# openSipPuff.net
KiCad netlist of a schematic drawn in EAGLE
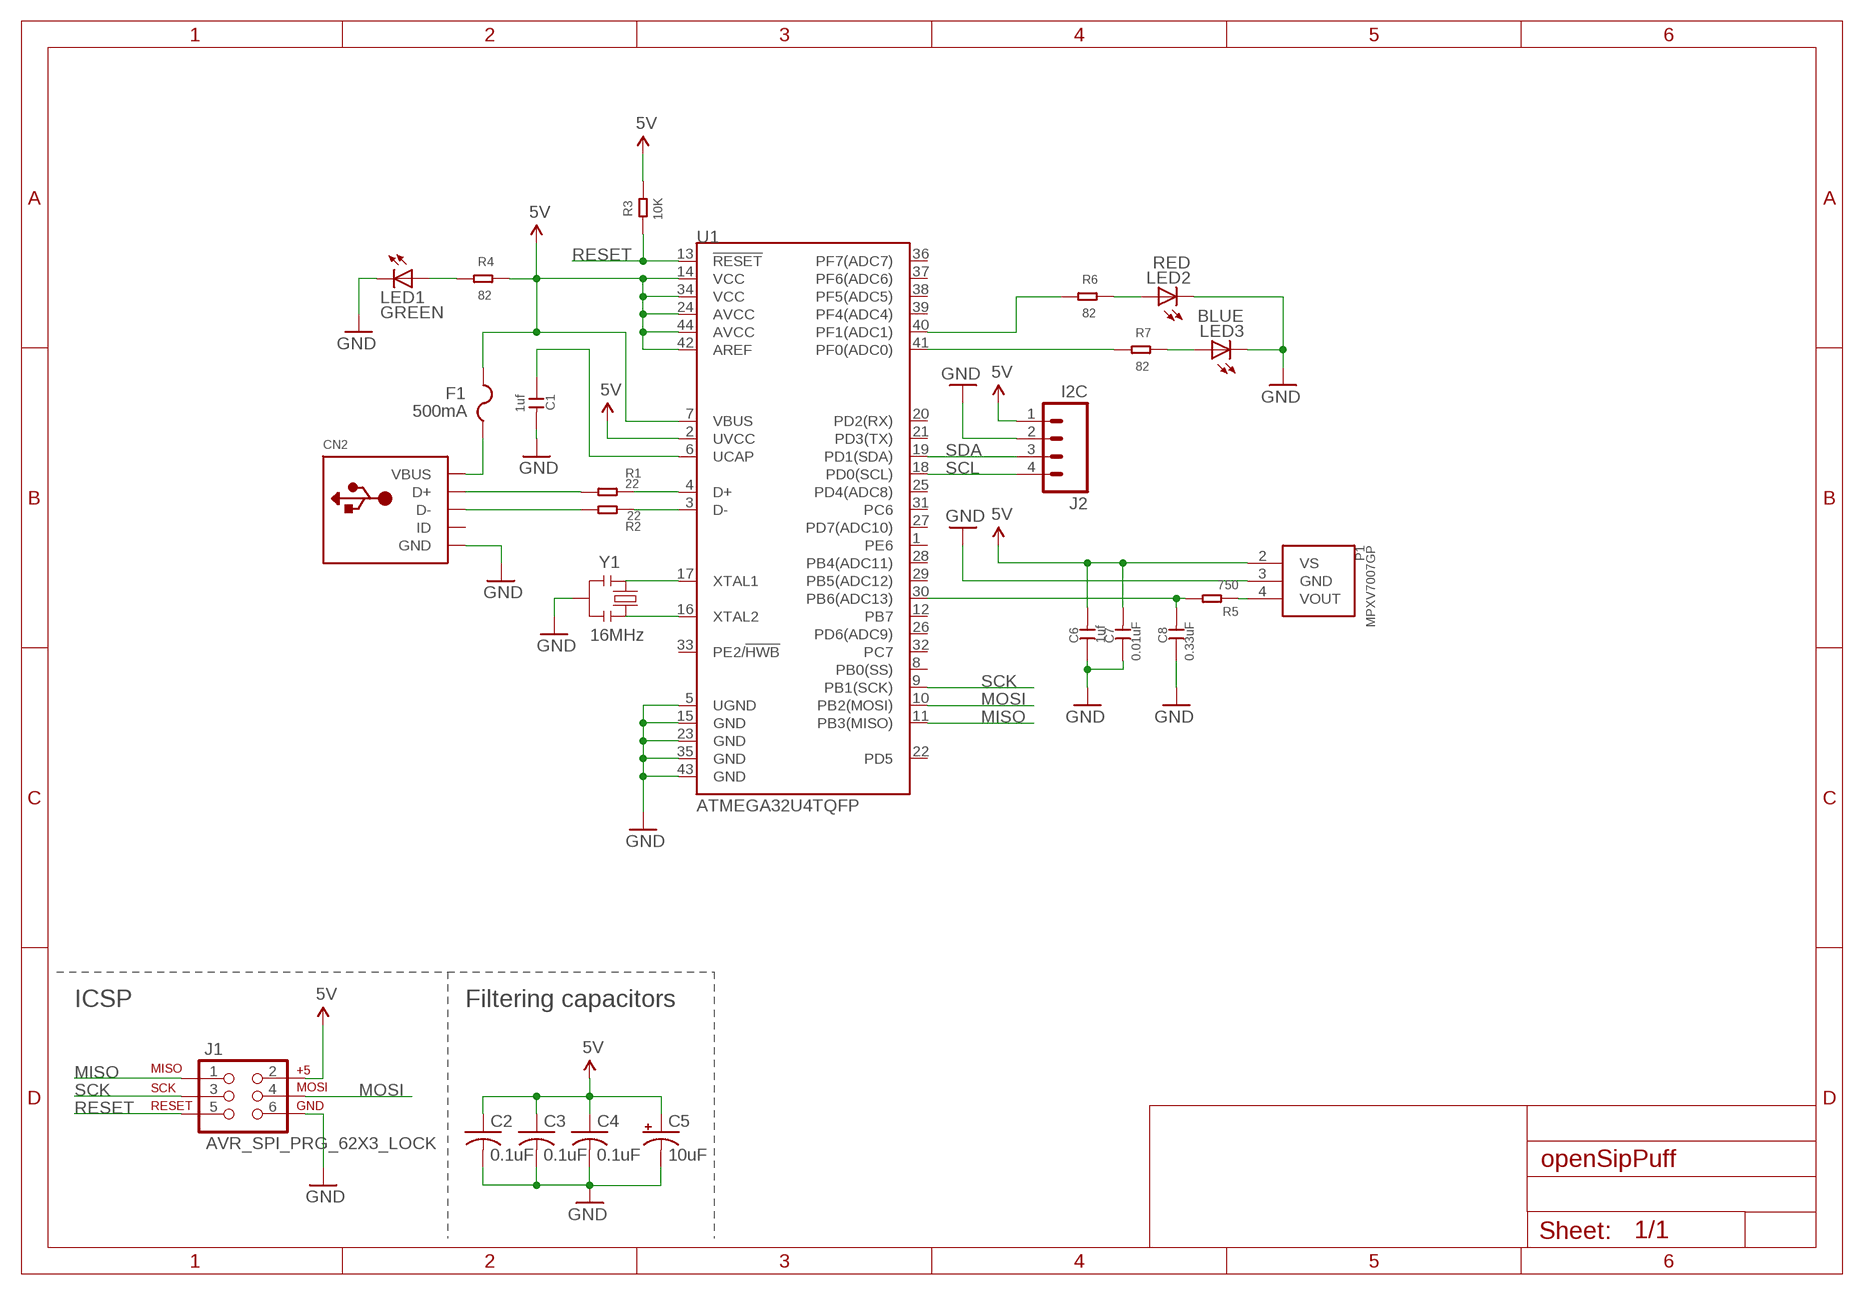
[diagram p0: schematic, sheet 1]

(export (version "E")
  (design (tool "Eeschema 10.0.6"))
  (components
    (comp (ref "C1")
      (value "1uf")
      (footprint "eagle-import:C0805")
      (fields (field (name "MPN") "CC0805KKX7R8BB105"))
      (libsource (lib "eagle-import") (part "CERAMIC-1UF-25V-10%-X7R(0805)"))
    )
    (comp (ref "C2")
      (value "0.1uF")
      (footprint "eagle-import:C0805K")
      (libsource (lib "eagle-import") (part "C-USC0805K"))
    )
    (comp (ref "C3")
      (value "0.1uF")
      (footprint "eagle-import:C0805K")
      (libsource (lib "eagle-import") (part "C-USC0805K"))
    )
    (comp (ref "C4")
      (value "0.1uF")
      (footprint "eagle-import:C0805K")
      (libsource (lib "eagle-import") (part "C-USC0805K"))
    )
    (comp (ref "C5")
      (value "10uF")
      (footprint "eagle-import:A_3216-18R")
      (libsource (lib "eagle-import") (part "CPOL-USA/3216-18R"))
    )
    (comp (ref "C6")
      (value "1uf")
      (footprint "eagle-import:C0805")
      (fields (field (name "MPN") "CC0805KKX7R8BB105"))
      (libsource (lib "eagle-import") (part "CERAMIC-1UF-25V-10%-X7R(0805)"))
    )
    (comp (ref "C7")
      (value "0.01uF")
      (footprint "eagle-import:C0805")
      (fields (field (name "MPN") "CC0805JRX7R9BB103"))
      (libsource (lib "eagle-import") (part "CERAMIC-10NF-50V-5%-X7R(0805)"))
    )
    (comp (ref "C8")
      (value "0.33uF")
      (footprint "eagle-import:C0805")
      (fields (field (name "MPN") "CC0805JRX7R9BB103"))
      (libsource (lib "eagle-import") (part "CERAMIC-10NF-50V-5%-X7R(0805)"))
    )
    (comp (ref "CN2")
      (value "USBMINIB")
      (footprint "eagle-import:USB-MINIB")
      (libsource (lib "eagle-import") (part "USBMINIB"))
    )
    (comp (ref "F1")
      (value "500mA")
      (footprint "eagle-import:R1206")
      (libsource (lib "eagle-import") (part "PTCFUSE-1206"))
    )
    (comp (ref "J1")
      (value "AVR_SPI_PRG_62X3_LOCK")
      (footprint "eagle-import:2X3_LOCK")
      (libsource (lib "eagle-import") (part "AVR_SPI_PRG_62X3_LOCK"))
    )
    (comp (ref "J2")
      (value "I2C")
      (footprint "eagle-import:1X04")
      (libsource (lib "eagle-import") (part "M04PTH"))
    )
    (comp (ref "LED1")
      (value "GREEN")
      (footprint "eagle-import:CHIPLED_0805")
      (libsource (lib "eagle-import") (part "LEDCHIPLED_0805"))
    )
    (comp (ref "LED2")
      (value "RED")
      (footprint "eagle-import:CHIPLED_0805")
      (libsource (lib "eagle-import") (part "LEDCHIPLED_0805"))
    )
    (comp (ref "LED3")
      (value "BLUE")
      (footprint "eagle-import:CHIPLED_0805")
      (libsource (lib "eagle-import") (part "LEDCHIPLED_0805"))
    )
    (comp (ref "P1")
      (value "MPXV7007GP")
      (footprint "eagle-import:SOP8")
      (libsource (lib "eagle-import") (part "MPXV7007GP"))
    )
    (comp (ref "R1")
      (value "22")
      (footprint "eagle-import:R0805")
      (libsource (lib "eagle-import") (part "RES-0805"))
    )
    (comp (ref "R2")
      (value "22")
      (footprint "eagle-import:R0805")
      (libsource (lib "eagle-import") (part "RES-0805"))
    )
    (comp (ref "R3")
      (value "10K")
      (footprint "eagle-import:R0805")
      (fields (field (name "MPN") "RC0805FR-0710KL"))
      (libsource (lib "eagle-import") (part "SMD-RES-10K-1%-1/8W(0805)"))
    )
    (comp (ref "R4")
      (value "82")
      (footprint "eagle-import:R0805")
      (fields (field (name "MPN") "RL0805JR-070R1L"))
      (libsource (lib "eagle-import") (part "SMD-RES-0.1R-5%-1/8W(0805)"))
    )
    (comp (ref "R5")
      (value "750")
      (footprint "eagle-import:R0805")
      (fields (field (name "MPN") "RC0805JR-072K2L"))
      (libsource (lib "eagle-import") (part "SMD-RES-2.2K-5%-1/8W(0805)"))
    )
    (comp (ref "R6")
      (value "82")
      (footprint "eagle-import:R0805")
      (fields (field (name "MPN") "RC0805JR-072K2L"))
      (libsource (lib "eagle-import") (part "SMD-RES-2.2K-5%-1/8W(0805)"))
    )
    (comp (ref "R7")
      (value "82")
      (footprint "eagle-import:R0805")
      (fields (field (name "MPN") "RC0805JR-072K2L"))
      (libsource (lib "eagle-import") (part "SMD-RES-2.2K-5%-1/8W(0805)"))
    )
    (comp (ref "U1")
      (value "ATMEGA32U4TQFP")
      (footprint "eagle-import:SPARKFUN-DIGITALIC_TQFP44")
      (libsource (lib "eagle-import") (part "ATMEGA32U4TQFP"))
    )
    (comp (ref "Y1")
      (value "16MHz")
      (footprint "eagle-import:RESONATOR-SMD")
      (libsource (lib "eagle-import") (part "RESONATOR16MHZ"))
    )
  )
  (nets
    (net (code "1") (name "/MISO") (class "Default")
      (node (ref "J1") (pin "1") (pinfunction "1_1") (pintype "passive"))
      (node (ref "U1") (pin "11") (pinfunction "PB3(MISO)_11") (pintype "bidirectional"))
    )
    (net (code "2") (name "/MOSI") (class "Default")
      (node (ref "J1") (pin "4") (pinfunction "4_4") (pintype "passive"))
      (node (ref "U1") (pin "10") (pinfunction "PB2(MOSI)_10") (pintype "bidirectional"))
    )
    (net (code "3") (name "/RESET") (class "Default")
      (node (ref "J1") (pin "5") (pinfunction "5_5") (pintype "passive"))
      (node (ref "R3") (pin "1") (pinfunction "1_1") (pintype "passive"))
      (node (ref "U1") (pin "13") (pinfunction "~{RESET}_13") (pintype "bidirectional"))
    )
    (net (code "4") (name "/SCK") (class "Default")
      (node (ref "J1") (pin "3") (pinfunction "3_3") (pintype "passive"))
      (node (ref "U1") (pin "9") (pinfunction "PB1(SCK)_9") (pintype "bidirectional"))
    )
    (net (code "5") (name "/SCL") (class "Default")
      (node (ref "J2") (pin "4") (pinfunction "4_4") (pintype "passive"))
      (node (ref "U1") (pin "18") (pinfunction "PD0(SCL)_18") (pintype "bidirectional"))
    )
    (net (code "6") (name "/SDA") (class "Default")
      (node (ref "J2") (pin "3") (pinfunction "3_3") (pintype "passive"))
      (node (ref "U1") (pin "19") (pinfunction "PD1(SDA)_19") (pintype "bidirectional"))
    )
    (net (code "7") (name "5V") (class "Default")
      (node (ref "C2") (pin "1") (pinfunction "1_1") (pintype "passive"))
      (node (ref "C3") (pin "1") (pinfunction "1_1") (pintype "passive"))
      (node (ref "C4") (pin "1") (pinfunction "1_1") (pintype "passive"))
      (node (ref "C5") (pin "+") (pinfunction "+_+") (pintype "passive"))
      (node (ref "C6") (pin "2") (pinfunction "2_2") (pintype "passive"))
      (node (ref "C7") (pin "2") (pinfunction "2_2") (pintype "passive"))
      (node (ref "F1") (pin "2") (pinfunction "2_2") (pintype "passive"))
      (node (ref "J1") (pin "2") (pinfunction "2_2") (pintype "passive"))
      (node (ref "J2") (pin "1") (pinfunction "1_1") (pintype "passive"))
      (node (ref "P1") (pin "2") (pinfunction "VS_2") (pintype "bidirectional"))
      (node (ref "R3") (pin "2") (pinfunction "2_2") (pintype "passive"))
      (node (ref "R4") (pin "2") (pinfunction "2_2") (pintype "passive"))
      (node (ref "U1") (pin "14") (pinfunction "VCC_14") (pintype "bidirectional"))
      (node (ref "U1") (pin "2") (pinfunction "UVCC_2") (pintype "bidirectional"))
      (node (ref "U1") (pin "24") (pinfunction "AVCC_24") (pintype "bidirectional"))
      (node (ref "U1") (pin "34") (pinfunction "VCC_34") (pintype "bidirectional"))
      (node (ref "U1") (pin "42") (pinfunction "AREF_42") (pintype "bidirectional"))
      (node (ref "U1") (pin "44") (pinfunction "AVCC_44") (pintype "bidirectional"))
      (node (ref "U1") (pin "7") (pinfunction "VBUS_7") (pintype "bidirectional"))
    )
    (net (code "8") (name "GND") (class "Default")
      (node (ref "C1") (pin "2") (pinfunction "2_2") (pintype "passive"))
      (node (ref "C2") (pin "2") (pinfunction "2_2") (pintype "passive"))
      (node (ref "C3") (pin "2") (pinfunction "2_2") (pintype "passive"))
      (node (ref "C4") (pin "2") (pinfunction "2_2") (pintype "passive"))
      (node (ref "C5") (pin "-") (pinfunction "-_-") (pintype "passive"))
      (node (ref "C6") (pin "1") (pinfunction "1_1") (pintype "passive"))
      (node (ref "C7") (pin "1") (pinfunction "1_1") (pintype "passive"))
      (node (ref "C8") (pin "1") (pinfunction "1_1") (pintype "passive"))
      (node (ref "CN2") (pin "GND") (pinfunction "GND_GND") (pintype "power_in"))
      (node (ref "J1") (pin "6") (pinfunction "6_6") (pintype "passive"))
      (node (ref "J2") (pin "2") (pinfunction "2_2") (pintype "passive"))
      (node (ref "LED1") (pin "C") (pinfunction "C_C") (pintype "passive"))
      (node (ref "LED2") (pin "C") (pinfunction "C_C") (pintype "passive"))
      (node (ref "LED3") (pin "C") (pinfunction "C_C") (pintype "passive"))
      (node (ref "P1") (pin "3") (pinfunction "GND_3") (pintype "bidirectional"))
      (node (ref "U1") (pin "15") (pinfunction "GND_15") (pintype "bidirectional"))
      (node (ref "U1") (pin "23") (pinfunction "GND_23") (pintype "bidirectional"))
      (node (ref "U1") (pin "35") (pinfunction "GND_35") (pintype "bidirectional"))
      (node (ref "U1") (pin "43") (pinfunction "GND_43") (pintype "bidirectional"))
      (node (ref "U1") (pin "5") (pinfunction "UGND_5") (pintype "bidirectional"))
      (node (ref "Y1") (pin "2") (pinfunction "2_2") (pintype "passive"))
    )
    (net (code "9") (name "Net-(CN2-PadD+)") (class "Default")
      (node (ref "CN2") (pin "D+") (pinfunction "D+_D+") (pintype "bidirectional"))
      (node (ref "R1") (pin "1") (pinfunction "1_1") (pintype "passive"))
    )
    (net (code "10") (name "Net-(CN2-PadD-)") (class "Default")
      (node (ref "CN2") (pin "D-") (pinfunction "D-_D-") (pintype "bidirectional"))
      (node (ref "R2") (pin "1") (pinfunction "1_1") (pintype "passive"))
    )
    (net (code "11") (name "Net-(CN2-PadVBUS)") (class "Default")
      (node (ref "CN2") (pin "VBUS") (pinfunction "VBUS_VBUS") (pintype "power_in"))
      (node (ref "F1") (pin "1") (pinfunction "1_1") (pintype "passive"))
    )
    (net (code "12") (name "Net-(LED1-PadA)") (class "Default")
      (node (ref "LED1") (pin "A") (pinfunction "A_A") (pintype "passive"))
      (node (ref "R4") (pin "1") (pinfunction "1_1") (pintype "passive"))
    )
    (net (code "13") (name "Net-(LED2-PadA)") (class "Default")
      (node (ref "LED2") (pin "A") (pinfunction "A_A") (pintype "passive"))
      (node (ref "R6") (pin "2") (pinfunction "2_2") (pintype "passive"))
    )
    (net (code "14") (name "Net-(LED3-PadA)") (class "Default")
      (node (ref "LED3") (pin "A") (pinfunction "A_A") (pintype "passive"))
      (node (ref "R7") (pin "2") (pinfunction "2_2") (pintype "passive"))
    )
    (net (code "15") (name "Net-(P1-VOUT)") (class "Default")
      (node (ref "P1") (pin "4") (pinfunction "VOUT_4") (pintype "bidirectional"))
      (node (ref "R5") (pin "1") (pinfunction "1_1") (pintype "passive"))
    )
    (net (code "16") (name "Net-(U1-D+)") (class "Default")
      (node (ref "R1") (pin "2") (pinfunction "2_2") (pintype "passive"))
      (node (ref "U1") (pin "4") (pinfunction "D+_4") (pintype "bidirectional"))
    )
    (net (code "17") (name "Net-(U1-D-)") (class "Default")
      (node (ref "R2") (pin "2") (pinfunction "2_2") (pintype "passive"))
      (node (ref "U1") (pin "3") (pinfunction "D-_3") (pintype "bidirectional"))
    )
    (net (code "18") (name "Net-(U1-PB6(ADC13))") (class "Default")
      (node (ref "C8") (pin "2") (pinfunction "2_2") (pintype "passive"))
      (node (ref "R5") (pin "2") (pinfunction "2_2") (pintype "passive"))
      (node (ref "U1") (pin "30") (pinfunction "PB6(ADC13)_30") (pintype "bidirectional"))
    )
    (net (code "19") (name "Net-(U1-PF0(ADC0))") (class "Default")
      (node (ref "R7") (pin "1") (pinfunction "1_1") (pintype "passive"))
      (node (ref "U1") (pin "41") (pinfunction "PF0(ADC0)_41") (pintype "bidirectional"))
    )
    (net (code "20") (name "Net-(U1-PF1(ADC1))") (class "Default")
      (node (ref "R6") (pin "1") (pinfunction "1_1") (pintype "passive"))
      (node (ref "U1") (pin "40") (pinfunction "PF1(ADC1)_40") (pintype "bidirectional"))
    )
    (net (code "21") (name "Net-(U1-UCAP)") (class "Default")
      (node (ref "C1") (pin "1") (pinfunction "1_1") (pintype "passive"))
      (node (ref "U1") (pin "6") (pinfunction "UCAP_6") (pintype "bidirectional"))
    )
    (net (code "22") (name "Net-(U1-XTAL1)") (class "Default")
      (node (ref "U1") (pin "17") (pinfunction "XTAL1_17") (pintype "bidirectional"))
      (node (ref "Y1") (pin "1") (pinfunction "1_1") (pintype "passive"))
    )
    (net (code "23") (name "Net-(U1-XTAL2)") (class "Default")
      (node (ref "U1") (pin "16") (pinfunction "XTAL2_16") (pintype "bidirectional"))
      (node (ref "Y1") (pin "3") (pinfunction "3_3") (pintype "passive"))
    )
    (net (code "24") (name "unconnected-(CN2-PadID)") (class "Default")
      (node (ref "CN2") (pin "ID") (pinfunction "ID_ID") (pintype "bidirectional"))
    )
    (net (code "25") (name "unconnected-(U1-PB0(SS)-Pad8)") (class "Default")
      (node (ref "U1") (pin "8") (pinfunction "PB0(SS)_8") (pintype "bidirectional"))
    )
    (net (code "26") (name "unconnected-(U1-PB4(ADC11)-Pad28)") (class "Default")
      (node (ref "U1") (pin "28") (pinfunction "PB4(ADC11)_28") (pintype "bidirectional"))
    )
    (net (code "27") (name "unconnected-(U1-PB5(ADC12)-Pad29)") (class "Default")
      (node (ref "U1") (pin "29") (pinfunction "PB5(ADC12)_29") (pintype "bidirectional"))
    )
    (net (code "28") (name "unconnected-(U1-PB7-Pad12)") (class "Default")
      (node (ref "U1") (pin "12") (pinfunction "PB7_12") (pintype "bidirectional"))
    )
    (net (code "29") (name "unconnected-(U1-PC6-Pad31)") (class "Default")
      (node (ref "U1") (pin "31") (pinfunction "PC6_31") (pintype "bidirectional"))
    )
    (net (code "30") (name "unconnected-(U1-PC7-Pad32)") (class "Default")
      (node (ref "U1") (pin "32") (pinfunction "PC7_32") (pintype "bidirectional"))
    )
    (net (code "31") (name "unconnected-(U1-PD2(RX)-Pad20)") (class "Default")
      (node (ref "U1") (pin "20") (pinfunction "PD2(RX)_20") (pintype "bidirectional"))
    )
    (net (code "32") (name "unconnected-(U1-PD3(TX)-Pad21)") (class "Default")
      (node (ref "U1") (pin "21") (pinfunction "PD3(TX)_21") (pintype "bidirectional"))
    )
    (net (code "33") (name "unconnected-(U1-PD4(ADC8)-Pad25)") (class "Default")
      (node (ref "U1") (pin "25") (pinfunction "PD4(ADC8)_25") (pintype "bidirectional"))
    )
    (net (code "34") (name "unconnected-(U1-PD5-Pad22)") (class "Default")
      (node (ref "U1") (pin "22") (pinfunction "PD5_22") (pintype "bidirectional"))
    )
    (net (code "35") (name "unconnected-(U1-PD6(ADC9)-Pad26)") (class "Default")
      (node (ref "U1") (pin "26") (pinfunction "PD6(ADC9)_26") (pintype "bidirectional"))
    )
    (net (code "36") (name "unconnected-(U1-PD7(ADC10)-Pad27)") (class "Default")
      (node (ref "U1") (pin "27") (pinfunction "PD7(ADC10)_27") (pintype "bidirectional"))
    )
    (net (code "37") (name "unconnected-(U1-PE2{slash}~{HWB}-Pad33)") (class "Default")
      (node (ref "U1") (pin "33") (pinfunction "PE2/~{HWB}_33") (pintype "bidirectional"))
    )
    (net (code "38") (name "unconnected-(U1-PE6-Pad1)") (class "Default")
      (node (ref "U1") (pin "1") (pinfunction "PE6_1") (pintype "bidirectional"))
    )
    (net (code "39") (name "unconnected-(U1-PF4(ADC4)-Pad39)") (class "Default")
      (node (ref "U1") (pin "39") (pinfunction "PF4(ADC4)_39") (pintype "bidirectional"))
    )
    (net (code "40") (name "unconnected-(U1-PF5(ADC5)-Pad38)") (class "Default")
      (node (ref "U1") (pin "38") (pinfunction "PF5(ADC5)_38") (pintype "bidirectional"))
    )
    (net (code "41") (name "unconnected-(U1-PF6(ADC6)-Pad37)") (class "Default")
      (node (ref "U1") (pin "37") (pinfunction "PF6(ADC6)_37") (pintype "bidirectional"))
    )
    (net (code "42") (name "unconnected-(U1-PF7(ADC7)-Pad36)") (class "Default")
      (node (ref "U1") (pin "36") (pinfunction "PF7(ADC7)_36") (pintype "bidirectional"))
    )
  )
)
